# EN-C200_RA0_PWR.net
KiCad netlist of a schematic drawn in Altium Designer
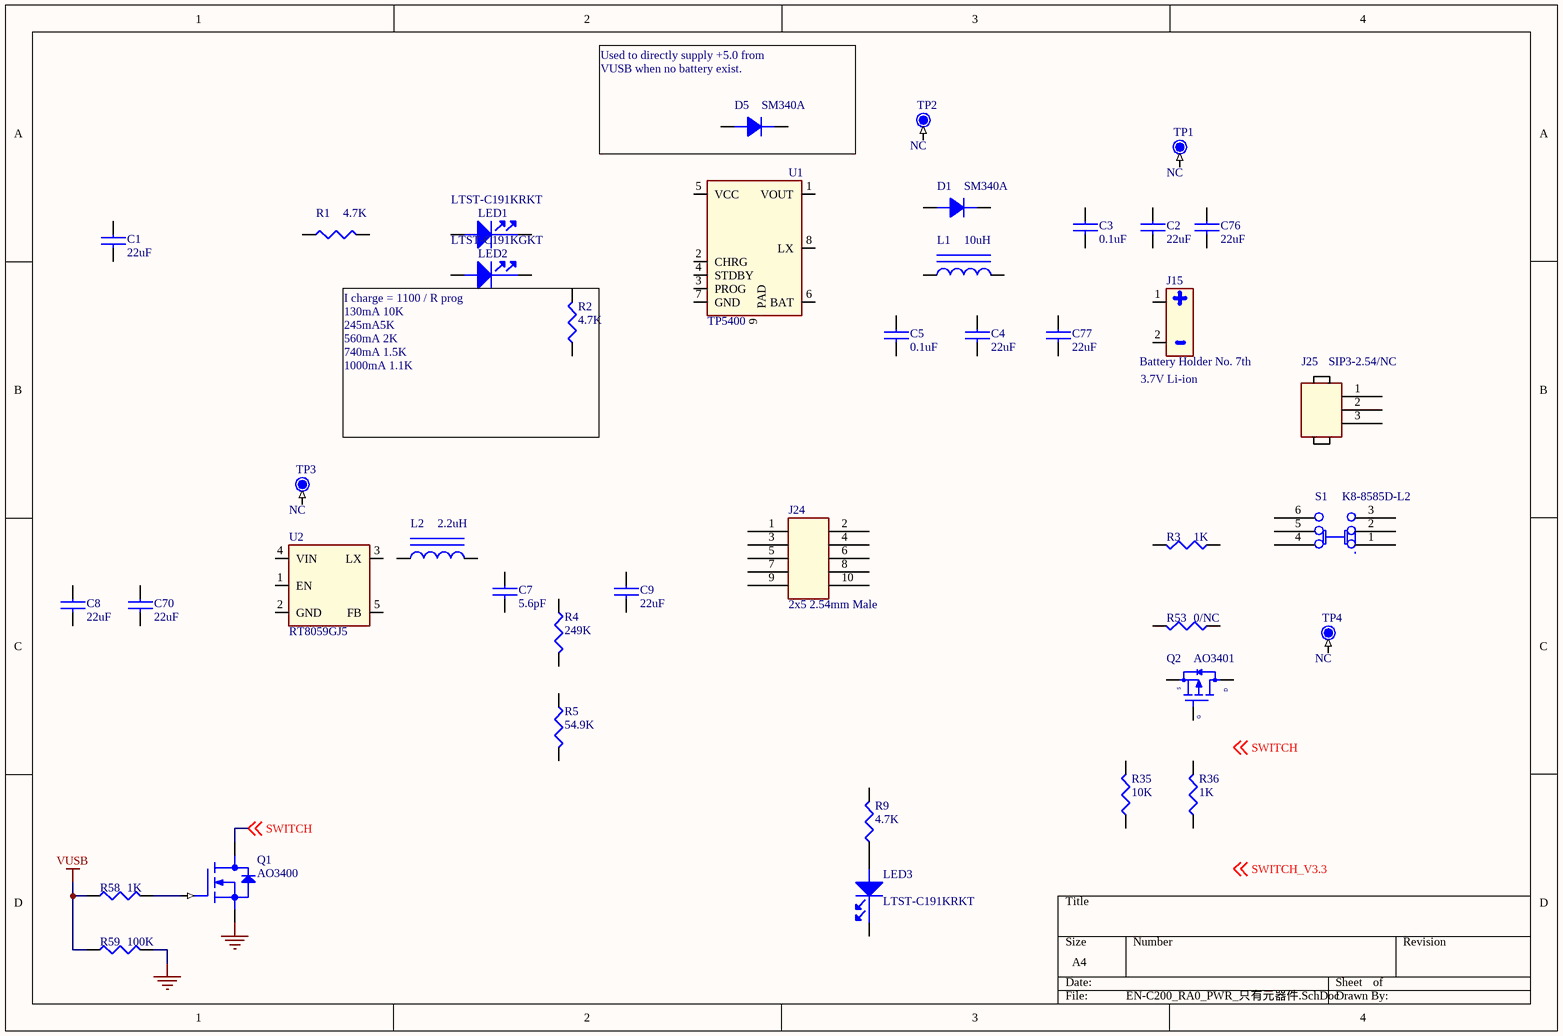
[diagram p0: EN-C200_RA0_PWR_只有元器件.SchDoc]

(export (version "E")
  (design (tool "Eeschema 10.0.6"))
  (components
    (comp (ref "C1") (value "22uF") (footprint "SC0805") (libsource (lib "EN-C200_RA0") (part "CAP NP")))
    (comp (ref "C2") (value "22uF") (footprint "SC0805") (libsource (lib "EN-C200_RA0") (part "CAP NP")))
    (comp (ref "C3") (value "0.1uF") (footprint "SC0603") (libsource (lib "EN-C200_RA0") (part "CAP NP")))
    (comp (ref "C4") (value "22uF") (footprint "SC0805") (libsource (lib "EN-C200_RA0") (part "CAP NP")))
    (comp (ref "C5") (value "0.1uF") (footprint "SC0603") (libsource (lib "EN-C200_RA0") (part "CAP NP")))
    (comp (ref "C7") (value "5.6pF") (footprint "SC0603") (libsource (lib "EN-C200_RA0") (part "CAP NP")))
    (comp (ref "C8") (value "22uF") (footprint "SC0805") (libsource (lib "EN-C200_RA0") (part "CAP NP")))
    (comp (ref "C9") (value "22uF") (footprint "SC0805") (libsource (lib "EN-C200_RA0") (part "CAP NP")))
    (comp (ref "C70") (value "22uF") (footprint "SC0805") (libsource (lib "EN-C200_RA0") (part "CAP NP")))
    (comp (ref "C76") (value "22uF") (footprint "SC0805") (libsource (lib "EN-C200_RA0") (part "CAP NP")))
    (comp (ref "C77") (value "22uF") (footprint "SC0805") (libsource (lib "EN-C200_RA0") (part "CAP NP")))
    (comp (ref "D1") (value "SM340A") (footprint "SD1714") (libsource (lib "EN-C200_RA0") (part "DIODE")))
    (comp (ref "D5") (value "SM340A") (footprint "SD1714") (libsource (lib "EN-C200_RA0") (part "DIODE")))
    (comp (ref "J15")
      (value "Battery Holder No. 7th")
      (footprint "BX0034")
      (libsource (lib "EN-C200_RA0") (part "BX0034"))
    )
    (comp (ref "J24")
      (value "2x5 2.54mm Male")
      (footprint "SIP-2X5P-100")
      (libsource (lib "EN-C200_RA0") (part "CON10A"))
    )
    (comp (ref "J25")
      (value "SIP3-2.54/NC")
      (footprint "SIP-3P")
      (libsource (lib "EN-C200_RA0") (part "HEADER3"))
    )
    (comp (ref "L1")
      (value "10uH")
      (footprint "SPL0505B")
      (libsource (lib "EN-C200_RA0") (part "TOROID IRON"))
    )
    (comp (ref "L2")
      (value "2.2uH")
      (footprint "SL1008")
      (libsource (lib "EN-C200_RA0") (part "TOROID IRON"))
    )
    (comp (ref "LED1")
      (value "LTST-C191KRKT")
      (footprint "HSD0603-LED")
      (libsource (lib "EN-C200_RA0") (part "LED"))
    )
    (comp (ref "LED2")
      (value "LTST-C191KGKT")
      (footprint "HSD0603-LED")
      (libsource (lib "EN-C200_RA0") (part "LED"))
    )
    (comp (ref "LED3")
      (value "LTST-C191KRKT")
      (footprint "HSD0603-LED")
      (libsource (lib "EN-C200_RA0") (part "LED"))
    )
    (comp (ref "Q1") (value "AO3400") (footprint "SOT23") (libsource (lib "EN-C200_RA0") (part "MPF6661")))
    (comp (ref "Q2") (value "AO3401") (footprint "SOT23") (libsource (lib "EN-C200_RA0") (part "A03401")))
    (comp (ref "R1") (value "4.7K") (footprint "SR0603") (libsource (lib "EN-C200_RA0") (part "RESISTOR")))
    (comp (ref "R2") (value "4.7K") (footprint "SR0603") (libsource (lib "EN-C200_RA0") (part "RESISTOR")))
    (comp (ref "R3") (value "1K") (footprint "SR0603") (libsource (lib "EN-C200_RA0") (part "RESISTOR")))
    (comp (ref "R4") (value "249K") (footprint "SR0603") (libsource (lib "EN-C200_RA0") (part "RESISTOR")))
    (comp (ref "R5") (value "54.9K") (footprint "SR0603") (libsource (lib "EN-C200_RA0") (part "RESISTOR")))
    (comp (ref "R9") (value "4.7K") (footprint "SR0603") (libsource (lib "EN-C200_RA0") (part "RESISTOR")))
    (comp (ref "R35") (value "10K") (footprint "SR0603") (libsource (lib "EN-C200_RA0") (part "RESISTOR")))
    (comp (ref "R36") (value "1K") (footprint "SR0603") (libsource (lib "EN-C200_RA0") (part "RESISTOR")))
    (comp (ref "R53") (value "0/NC") (footprint "SR0603") (libsource (lib "EN-C200_RA0") (part "RESISTOR")))
    (comp (ref "R58") (value "1K") (footprint "SR0603") (libsource (lib "EN-C200_RA0") (part "RESISTOR")))
    (comp (ref "R59") (value "100K") (footprint "SR0603") (libsource (lib "EN-C200_RA0") (part "RESISTOR")))
    (comp (ref "S1")
      (value "K8-8585D-L2")
      (footprint "SW2X3-100")
      (libsource (lib "EN-C200_RA0") (part "SW_PUSH6"))
    )
    (comp (ref "TP1") (value "NC") (footprint "TP32-SMD") (libsource (lib "EN-C200_RA0") (part "TP")))
    (comp (ref "TP2") (value "NC") (footprint "TP32-SMD") (libsource (lib "EN-C200_RA0") (part "TP")))
    (comp (ref "TP3") (value "NC") (footprint "TP32-SMD") (libsource (lib "EN-C200_RA0") (part "TP")))
    (comp (ref "TP4") (value "NC") (footprint "TP32-SMD") (libsource (lib "EN-C200_RA0") (part "TP")))
    (comp (ref "U1")
      (value "TP5400")
      (footprint "SOP8-50-150B")
      (libsource (lib "EN-C200_RA0") (part "TP5400"))
    )
    (comp (ref "U2")
      (value "RT8059GJ5")
      (footprint "SOT23-5")
      (libsource (lib "EN-C200_RA0") (part "RT8059"))
    )
  )
  (nets
    (net (code "1") (name "GND") (class "Default")
      (node (ref "Q1") (pin "2") (pinfunction "S_2") (pintype "passive"))
      (node (ref "R59") (pin "2") (pinfunction "2_2") (pintype "passive"))
    )
    (net (code "2") (name "Net-(LED3-Pad1)") (class "Default")
      (node (ref "LED3") (pin "1") (pinfunction "1_1") (pintype "passive"))
      (node (ref "R9") (pin "1") (pinfunction "1_1") (pintype "passive"))
    )
    (net (code "3") (name "Net-(Q1-G)") (class "Default")
      (node (ref "Q1") (pin "1") (pinfunction "G_1") (pintype "input"))
      (node (ref "R58") (pin "2") (pinfunction "2_2") (pintype "passive"))
    )
    (net (code "4") (name "SWITCH") (class "Default")
      (node (ref "Q1") (pin "3") (pinfunction "D_3") (pintype "passive"))
    )
    (net (code "6") (name "VUSB") (class "Default")
      (node (ref "R58") (pin "1") (pinfunction "1_1") (pintype "passive"))
      (node (ref "R59") (pin "1") (pinfunction "1_1") (pintype "passive"))
    )
    (net (code "7") (name "unconnected-(C1-Pad1)") (class "Default")
      (node (ref "C1") (pin "1") (pinfunction "1_1") (pintype "passive"))
    )
    (net (code "8") (name "unconnected-(C1-Pad2)") (class "Default")
      (node (ref "C1") (pin "2") (pinfunction "2_2") (pintype "passive"))
    )
    (net (code "9") (name "unconnected-(C2-Pad1)") (class "Default")
      (node (ref "C2") (pin "1") (pinfunction "1_1") (pintype "passive"))
    )
    (net (code "10") (name "unconnected-(C2-Pad2)") (class "Default")
      (node (ref "C2") (pin "2") (pinfunction "2_2") (pintype "passive"))
    )
    (net (code "11") (name "unconnected-(C3-Pad1)") (class "Default")
      (node (ref "C3") (pin "1") (pinfunction "1_1") (pintype "passive"))
    )
    (net (code "12") (name "unconnected-(C3-Pad2)") (class "Default")
      (node (ref "C3") (pin "2") (pinfunction "2_2") (pintype "passive"))
    )
    (net (code "13") (name "unconnected-(C4-Pad1)") (class "Default")
      (node (ref "C4") (pin "1") (pinfunction "1_1") (pintype "passive"))
    )
    (net (code "14") (name "unconnected-(C4-Pad2)") (class "Default")
      (node (ref "C4") (pin "2") (pinfunction "2_2") (pintype "passive"))
    )
    (net (code "15") (name "unconnected-(C5-Pad1)") (class "Default")
      (node (ref "C5") (pin "1") (pinfunction "1_1") (pintype "passive"))
    )
    (net (code "16") (name "unconnected-(C5-Pad2)") (class "Default")
      (node (ref "C5") (pin "2") (pinfunction "2_2") (pintype "passive"))
    )
    (net (code "17") (name "unconnected-(C7-Pad1)") (class "Default")
      (node (ref "C7") (pin "1") (pinfunction "1_1") (pintype "passive"))
    )
    (net (code "18") (name "unconnected-(C7-Pad2)") (class "Default")
      (node (ref "C7") (pin "2") (pinfunction "2_2") (pintype "passive"))
    )
    (net (code "19") (name "unconnected-(C8-Pad1)") (class "Default")
      (node (ref "C8") (pin "1") (pinfunction "1_1") (pintype "passive"))
    )
    (net (code "20") (name "unconnected-(C8-Pad2)") (class "Default")
      (node (ref "C8") (pin "2") (pinfunction "2_2") (pintype "passive"))
    )
    (net (code "21") (name "unconnected-(C9-Pad1)") (class "Default")
      (node (ref "C9") (pin "1") (pinfunction "1_1") (pintype "passive"))
    )
    (net (code "22") (name "unconnected-(C9-Pad2)") (class "Default")
      (node (ref "C9") (pin "2") (pinfunction "2_2") (pintype "passive"))
    )
    (net (code "23") (name "unconnected-(C70-Pad1)") (class "Default")
      (node (ref "C70") (pin "1") (pinfunction "1_1") (pintype "passive"))
    )
    (net (code "24") (name "unconnected-(C70-Pad2)") (class "Default")
      (node (ref "C70") (pin "2") (pinfunction "2_2") (pintype "passive"))
    )
    (net (code "25") (name "unconnected-(C76-Pad1)") (class "Default")
      (node (ref "C76") (pin "1") (pinfunction "1_1") (pintype "passive"))
    )
    (net (code "26") (name "unconnected-(C76-Pad2)") (class "Default")
      (node (ref "C76") (pin "2") (pinfunction "2_2") (pintype "passive"))
    )
    (net (code "27") (name "unconnected-(C77-Pad1)") (class "Default")
      (node (ref "C77") (pin "1") (pinfunction "1_1") (pintype "passive"))
    )
    (net (code "28") (name "unconnected-(C77-Pad2)") (class "Default")
      (node (ref "C77") (pin "2") (pinfunction "2_2") (pintype "passive"))
    )
    (net (code "29") (name "unconnected-(D1-A-Pad1)") (class "Default")
      (node (ref "D1") (pin "1") (pinfunction "A_1") (pintype "passive"))
    )
    (net (code "30") (name "unconnected-(D1-K-Pad2)") (class "Default")
      (node (ref "D1") (pin "2") (pinfunction "K_2") (pintype "passive"))
    )
    (net (code "31") (name "unconnected-(D5-A-Pad1)") (class "Default")
      (node (ref "D5") (pin "1") (pinfunction "A_1") (pintype "passive"))
    )
    (net (code "32") (name "unconnected-(D5-K-Pad2)") (class "Default")
      (node (ref "D5") (pin "2") (pinfunction "K_2") (pintype "passive"))
    )
    (net (code "33") (name "unconnected-(J15-Pad1)") (class "Default")
      (node (ref "J15") (pin "1") (pinfunction "1_1") (pintype "passive"))
    )
    (net (code "34") (name "unconnected-(J15-Pad2)") (class "Default")
      (node (ref "J15") (pin "2") (pinfunction "2_2") (pintype "passive"))
    )
    (net (code "35") (name "unconnected-(J24-Pad1)") (class "Default")
      (node (ref "J24") (pin "1") (pinfunction "1_1") (pintype "passive"))
    )
    (net (code "36") (name "unconnected-(J24-Pad2)") (class "Default")
      (node (ref "J24") (pin "2") (pinfunction "2_2") (pintype "passive"))
    )
    (net (code "37") (name "unconnected-(J24-Pad3)") (class "Default")
      (node (ref "J24") (pin "3") (pinfunction "3_3") (pintype "passive"))
    )
    (net (code "38") (name "unconnected-(J24-Pad4)") (class "Default")
      (node (ref "J24") (pin "4") (pinfunction "4_4") (pintype "passive"))
    )
    (net (code "39") (name "unconnected-(J24-Pad5)") (class "Default")
      (node (ref "J24") (pin "5") (pinfunction "5_5") (pintype "passive"))
    )
    (net (code "40") (name "unconnected-(J24-Pad6)") (class "Default")
      (node (ref "J24") (pin "6") (pinfunction "6_6") (pintype "passive"))
    )
    (net (code "41") (name "unconnected-(J24-Pad7)") (class "Default")
      (node (ref "J24") (pin "7") (pinfunction "7_7") (pintype "passive"))
    )
    (net (code "42") (name "unconnected-(J24-Pad8)") (class "Default")
      (node (ref "J24") (pin "8") (pinfunction "8_8") (pintype "passive"))
    )
    (net (code "43") (name "unconnected-(J24-Pad9)") (class "Default")
      (node (ref "J24") (pin "9") (pinfunction "9_9") (pintype "passive"))
    )
    (net (code "44") (name "unconnected-(J24-Pad10)") (class "Default")
      (node (ref "J24") (pin "10") (pinfunction "10_10") (pintype "passive"))
    )
    (net (code "45") (name "unconnected-(J25-Pad1)") (class "Default")
      (node (ref "J25") (pin "1") (pinfunction "1_1") (pintype "passive"))
    )
    (net (code "46") (name "unconnected-(J25-Pad2)") (class "Default")
      (node (ref "J25") (pin "2") (pinfunction "2_2") (pintype "passive"))
    )
    (net (code "47") (name "unconnected-(J25-Pad3)") (class "Default")
      (node (ref "J25") (pin "3") (pinfunction "3_3") (pintype "passive"))
    )
    (net (code "48") (name "unconnected-(L1-Pad1)") (class "Default")
      (node (ref "L1") (pin "1") (pinfunction "1_1") (pintype "passive"))
    )
    (net (code "49") (name "unconnected-(L1-Pad2)") (class "Default")
      (node (ref "L1") (pin "2") (pinfunction "2_2") (pintype "passive"))
    )
    (net (code "50") (name "unconnected-(L2-Pad1)") (class "Default")
      (node (ref "L2") (pin "1") (pinfunction "1_1") (pintype "passive"))
    )
    (net (code "51") (name "unconnected-(L2-Pad2)") (class "Default")
      (node (ref "L2") (pin "2") (pinfunction "2_2") (pintype "passive"))
    )
    (net (code "52") (name "unconnected-(LED1-Pad1)") (class "Default")
      (node (ref "LED1") (pin "1") (pinfunction "1_1") (pintype "passive"))
    )
    (net (code "53") (name "unconnected-(LED1-Pad2)") (class "Default")
      (node (ref "LED1") (pin "2") (pinfunction "2_2") (pintype "passive"))
    )
    (net (code "54") (name "unconnected-(LED2-Pad1)") (class "Default")
      (node (ref "LED2") (pin "1") (pinfunction "1_1") (pintype "passive"))
    )
    (net (code "55") (name "unconnected-(LED2-Pad2)") (class "Default")
      (node (ref "LED2") (pin "2") (pinfunction "2_2") (pintype "passive"))
    )
    (net (code "56") (name "unconnected-(LED3-Pad2)") (class "Default")
      (node (ref "LED3") (pin "2") (pinfunction "2_2") (pintype "passive"))
    )
    (net (code "57") (name "unconnected-(Q2-D-Pad3)") (class "Default")
      (node (ref "Q2") (pin "3") (pinfunction "D_3") (pintype "passive"))
    )
    (net (code "58") (name "unconnected-(Q2-G-Pad1)") (class "Default")
      (node (ref "Q2") (pin "1") (pinfunction "G_1") (pintype "passive"))
    )
    (net (code "59") (name "unconnected-(Q2-S-Pad2)") (class "Default")
      (node (ref "Q2") (pin "2") (pinfunction "S_2") (pintype "passive"))
    )
    (net (code "60") (name "unconnected-(R1-Pad1)") (class "Default")
      (node (ref "R1") (pin "1") (pinfunction "1_1") (pintype "passive"))
    )
    (net (code "61") (name "unconnected-(R1-Pad2)") (class "Default")
      (node (ref "R1") (pin "2") (pinfunction "2_2") (pintype "passive"))
    )
    (net (code "62") (name "unconnected-(R2-Pad1)") (class "Default")
      (node (ref "R2") (pin "1") (pinfunction "1_1") (pintype "passive"))
    )
    (net (code "63") (name "unconnected-(R2-Pad2)") (class "Default")
      (node (ref "R2") (pin "2") (pinfunction "2_2") (pintype "passive"))
    )
    (net (code "64") (name "unconnected-(R3-Pad1)") (class "Default")
      (node (ref "R3") (pin "1") (pinfunction "1_1") (pintype "passive"))
    )
    (net (code "65") (name "unconnected-(R3-Pad2)") (class "Default")
      (node (ref "R3") (pin "2") (pinfunction "2_2") (pintype "passive"))
    )
    (net (code "66") (name "unconnected-(R4-Pad1)") (class "Default")
      (node (ref "R4") (pin "1") (pinfunction "1_1") (pintype "passive"))
    )
    (net (code "67") (name "unconnected-(R4-Pad2)") (class "Default")
      (node (ref "R4") (pin "2") (pinfunction "2_2") (pintype "passive"))
    )
    (net (code "68") (name "unconnected-(R5-Pad1)") (class "Default")
      (node (ref "R5") (pin "1") (pinfunction "1_1") (pintype "passive"))
    )
    (net (code "69") (name "unconnected-(R5-Pad2)") (class "Default")
      (node (ref "R5") (pin "2") (pinfunction "2_2") (pintype "passive"))
    )
    (net (code "70") (name "unconnected-(R9-Pad2)") (class "Default")
      (node (ref "R9") (pin "2") (pinfunction "2_2") (pintype "passive"))
    )
    (net (code "71") (name "unconnected-(R35-Pad1)") (class "Default")
      (node (ref "R35") (pin "1") (pinfunction "1_1") (pintype "passive"))
    )
    (net (code "72") (name "unconnected-(R35-Pad2)") (class "Default")
      (node (ref "R35") (pin "2") (pinfunction "2_2") (pintype "passive"))
    )
    (net (code "73") (name "unconnected-(R36-Pad1)") (class "Default")
      (node (ref "R36") (pin "1") (pinfunction "1_1") (pintype "passive"))
    )
    (net (code "74") (name "unconnected-(R36-Pad2)") (class "Default")
      (node (ref "R36") (pin "2") (pinfunction "2_2") (pintype "passive"))
    )
    (net (code "75") (name "unconnected-(R53-Pad1)") (class "Default")
      (node (ref "R53") (pin "1") (pinfunction "1_1") (pintype "passive"))
    )
    (net (code "76") (name "unconnected-(R53-Pad2)") (class "Default")
      (node (ref "R53") (pin "2") (pinfunction "2_2") (pintype "passive"))
    )
    (net (code "77") (name "unconnected-(S1-Pad1)") (class "Default")
      (node (ref "S1") (pin "1") (pinfunction "1_1") (pintype "passive"))
    )
    (net (code "78") (name "unconnected-(S1-Pad2)") (class "Default")
      (node (ref "S1") (pin "2") (pinfunction "2_2") (pintype "passive"))
    )
    (net (code "79") (name "unconnected-(S1-Pad3)") (class "Default")
      (node (ref "S1") (pin "3") (pinfunction "3_3") (pintype "passive"))
    )
    (net (code "80") (name "unconnected-(S1-Pad4)") (class "Default")
      (node (ref "S1") (pin "4") (pinfunction "4_4") (pintype "passive"))
    )
    (net (code "81") (name "unconnected-(S1-Pad5)") (class "Default")
      (node (ref "S1") (pin "5") (pinfunction "5_5") (pintype "passive"))
    )
    (net (code "82") (name "unconnected-(S1-Pad6)") (class "Default")
      (node (ref "S1") (pin "6") (pinfunction "6_6") (pintype "passive"))
    )
    (net (code "83") (name "unconnected-(TP1-Pad1)") (class "Default")
      (node (ref "TP1") (pin "1") (pinfunction "1_1") (pintype "input"))
    )
    (net (code "84") (name "unconnected-(TP2-Pad1)") (class "Default")
      (node (ref "TP2") (pin "1") (pinfunction "1_1") (pintype "input"))
    )
    (net (code "85") (name "unconnected-(TP3-Pad1)") (class "Default")
      (node (ref "TP3") (pin "1") (pinfunction "1_1") (pintype "input"))
    )
    (net (code "86") (name "unconnected-(TP4-Pad1)") (class "Default")
      (node (ref "TP4") (pin "1") (pinfunction "1_1") (pintype "input"))
    )
    (net (code "87") (name "unconnected-(U1-BAT-Pad6)") (class "Default")
      (node (ref "U1") (pin "6") (pinfunction "BAT_6") (pintype "power_in"))
    )
    (net (code "88") (name "unconnected-(U1-CHRG-Pad2)") (class "Default")
      (node (ref "U1") (pin "2") (pinfunction "CHRG_2") (pintype "passive"))
    )
    (net (code "89") (name "unconnected-(U1-GND-Pad7)") (class "Default")
      (node (ref "U1") (pin "7") (pinfunction "GND_7") (pintype "power_in"))
    )
    (net (code "90") (name "unconnected-(U1-LX-Pad8)") (class "Default")
      (node (ref "U1") (pin "8") (pinfunction "LX_8") (pintype "passive"))
    )
    (net (code "91") (name "unconnected-(U1-PAD-Pad9)") (class "Default")
      (node (ref "U1") (pin "9") (pinfunction "PAD_9") (pintype "passive"))
    )
    (net (code "92") (name "unconnected-(U1-PROG-Pad3)") (class "Default")
      (node (ref "U1") (pin "3") (pinfunction "PROG_3") (pintype "passive"))
    )
    (net (code "93") (name "unconnected-(U1-STDBY-Pad4)") (class "Default")
      (node (ref "U1") (pin "4") (pinfunction "STDBY_4") (pintype "passive"))
    )
    (net (code "94") (name "unconnected-(U1-VCC-Pad5)") (class "Default")
      (node (ref "U1") (pin "5") (pinfunction "VCC_5") (pintype "power_in"))
    )
    (net (code "95") (name "unconnected-(U1-VOUT-Pad1)") (class "Default")
      (node (ref "U1") (pin "1") (pinfunction "VOUT_1") (pintype "power_in"))
    )
    (net (code "96") (name "unconnected-(U2-EN-Pad1)") (class "Default")
      (node (ref "U2") (pin "1") (pinfunction "EN_1") (pintype "passive"))
    )
    (net (code "97") (name "unconnected-(U2-FB-Pad5)") (class "Default")
      (node (ref "U2") (pin "5") (pinfunction "FB_5") (pintype "passive"))
    )
    (net (code "98") (name "unconnected-(U2-GND-Pad2)") (class "Default")
      (node (ref "U2") (pin "2") (pinfunction "GND_2") (pintype "power_in"))
    )
    (net (code "99") (name "unconnected-(U2-LX-Pad3)") (class "Default")
      (node (ref "U2") (pin "3") (pinfunction "LX_3") (pintype "passive"))
    )
    (net (code "100") (name "unconnected-(U2-VIN-Pad4)") (class "Default")
      (node (ref "U2") (pin "4") (pinfunction "VIN_4") (pintype "power_in"))
    )
  )
)
